# USB.net
KiCad netlist of a schematic drawn in Altium Designer
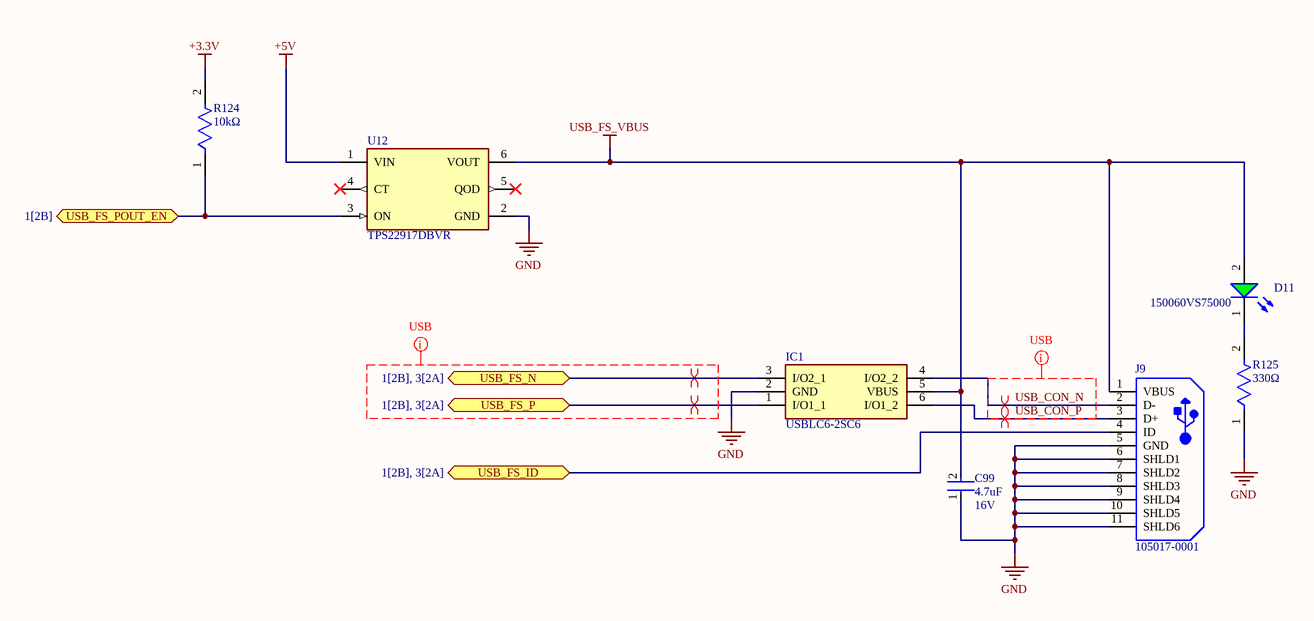
[diagram p0: USB.SchDoc]

(export (version "E")
  (design (tool "Eeschema 10.0.6"))
  (components
    (comp (ref "C99")
      (value "C1608X5R1C475K080AC")
      (footprint "FP-C1608-080-0_1-IPC_B")
      (description "Multilayer Ceramic Capacitors 4.7μF ±10% 16V X5R SMD 0603")
      (fields
        (field (name "TOLERANCE") "10%")
        (field (name "VOLTAGE") "16V")
        (field (name "CAPACITANCE") "4.7uF")
      )
      (libsource (lib "Altium Content Vault") (part "236180d848d6139a670b325ea6854c9"))
    )
    (comp (ref "D11")
      (value "150060VS75000")
      (footprint "WL-SMCW_0603_150060xx75000")
      (libsource (lib "Altium Content Vault") (part "LED_Green_2A-1K"))
    )
    (comp (ref "IC1")
      (value "USBLC6-2SC6")
      (footprint "SamacSys:SOT95P280X145-6N")
      (description "Integrated Circuit")
      (fields (field (name "MOUSER PART NUMBER") "511-USBLC6-2SC6"))
      (libsource (lib "*") (part "USBLC6-2SC6"))
    )
    (comp (ref "J9")
      (value "105017-0001")
      (footprint "USB-MICRO-B_V")
      (fields (field (name "MANUFACTURER") "Molex"))
      (libsource (lib "Altium Content Vault") (part "USB-5-6SHLD"))
    )
    (comp (ref "R124")
      (value "RC0603FR-0710KL")
      (footprint "FP-RC0603-0_55-IPC_B")
      (description "RES 10K OHM 1% 1/10W 0603")
      (fields (field (name "TOLERANCE") "1%") (field (name "RESISTANCE") "10kΩ"))
      (libsource (lib "Altium Content Vault") (part "1029c3af85768c4190bb7ad29bc67b5"))
    )
    (comp (ref "R125")
      (value "CRCW0603330RFKEA")
      (footprint "FP-CRCW0603-e3-MFG")
      (description "RES Thick Film, 330Ω, 1%, 0.1W, 100ppm/°C, 0603")
      (fields (field (name "TOLERANCE") "1%") (field (name "RESISTANCE") "330Ω"))
      (libsource (lib "Altium Content Vault") (part "1029c3af85768c4190bb7ad29bc67b5"))
    )
    (comp (ref "U12")
      (value "TPS22917DBVR")
      (footprint "FP-DBV0006A-MFG")
      (description "IC PWR SWITCH P-CHAN 1:1 SOT23-6")
      (libsource (lib "Altium Content Vault") (part "79ac4b3a8af48598f911740ea3eee0a"))
    )
  )
  (nets
    (net (code "1") (name "+3.3V") (class "Default")
      (node (ref "R124") (pin "2") (pinfunction "2_2") (pintype "passive"))
    )
    (net (code "2") (name "+5V") (class "Default")
      (node (ref "U12") (pin "1") (pinfunction "VIN_1") (pintype "passive"))
    )
    (net (code "3") (name "/USB_CON_N") (class "Default")
      (node (ref "IC1") (pin "4") (pinfunction "I/O2_2_4") (pintype "passive"))
      (node (ref "J9") (pin "2") (pinfunction "D-_2") (pintype "passive"))
    )
    (net (code "4") (name "/USB_CON_P") (class "Default")
      (node (ref "IC1") (pin "6") (pinfunction "I/O1_2_6") (pintype "passive"))
      (node (ref "J9") (pin "3") (pinfunction "D+_3") (pintype "passive"))
    )
    (net (code "5") (name "/USB_FS_ID") (class "Default")
      (node (ref "J9") (pin "4") (pinfunction "ID_4") (pintype "passive"))
    )
    (net (code "6") (name "/USB_FS_N") (class "Default")
      (node (ref "IC1") (pin "3") (pinfunction "I/O2_1_3") (pintype "passive"))
    )
    (net (code "7") (name "/USB_FS_P") (class "Default")
      (node (ref "IC1") (pin "1") (pinfunction "I/O1_1_1") (pintype "passive"))
    )
    (net (code "8") (name "/USB_FS_POUT_EN") (class "Default")
      (node (ref "R124") (pin "1") (pinfunction "1_1") (pintype "passive"))
      (node (ref "U12") (pin "3") (pinfunction "ON_3") (pintype "input"))
    )
    (net (code "9") (name "GND") (class "Default")
      (node (ref "C99") (pin "1") (pinfunction "1_1") (pintype "passive"))
      (node (ref "IC1") (pin "2") (pinfunction "GND_2") (pintype "passive"))
      (node (ref "J9") (pin "10") (pinfunction "SHLD5_10") (pintype "passive"))
      (node (ref "J9") (pin "11") (pinfunction "SHLD6_11") (pintype "passive"))
      (node (ref "J9") (pin "5") (pinfunction "GND_5") (pintype "passive"))
      (node (ref "J9") (pin "6") (pinfunction "SHLD1_6") (pintype "passive"))
      (node (ref "J9") (pin "7") (pinfunction "SHLD2_7") (pintype "passive"))
      (node (ref "J9") (pin "8") (pinfunction "SHLD3_8") (pintype "passive"))
      (node (ref "J9") (pin "9") (pinfunction "SHLD4_9") (pintype "passive"))
      (node (ref "R125") (pin "1") (pinfunction "1_1") (pintype "passive"))
      (node (ref "U12") (pin "2") (pinfunction "GND_2") (pintype "power_in"))
    )
    (net (code "10") (name "Net-(D11-K)") (class "Default")
      (node (ref "D11") (pin "1") (pinfunction "K_1") (pintype "passive"))
      (node (ref "R125") (pin "2") (pinfunction "2_2") (pintype "passive"))
    )
    (net (code "11") (name "USB_FS_VBUS") (class "Default")
      (node (ref "C99") (pin "2") (pinfunction "2_2") (pintype "passive"))
      (node (ref "D11") (pin "2") (pinfunction "A_2") (pintype "passive"))
      (node (ref "IC1") (pin "5") (pinfunction "VBUS_5") (pintype "passive"))
      (node (ref "J9") (pin "1") (pinfunction "VBUS_1") (pintype "passive"))
      (node (ref "U12") (pin "6") (pinfunction "VOUT_6") (pintype "passive"))
    )
    (net (code "12") (name "unconnected-(U12-CT-Pad4)") (class "Default")
      (node (ref "U12") (pin "4") (pinfunction "CT_4") (pintype "output+no_connect"))
    )
    (net (code "13") (name "unconnected-(U12-QOD-Pad5)") (class "Default")
      (node (ref "U12") (pin "5") (pinfunction "QOD_5") (pintype "output+no_connect"))
    )
  )
)
